# EFuse_5V.net
KiCad netlist of a schematic drawn in Altium Designer
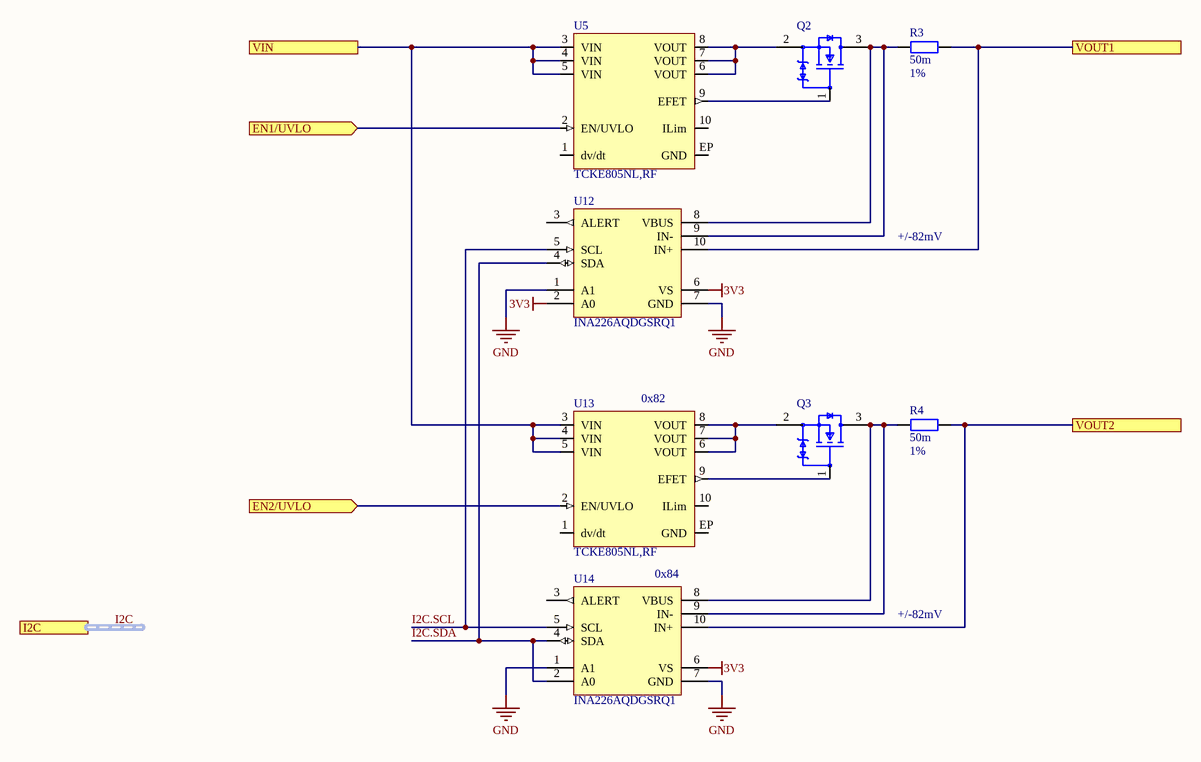
[diagram p0: EFuse_5V.SchDoc]

(export (version "E")
  (design (tool "Eeschema 10.0.6"))
  (components
    (comp (ref "Q2")
      (value "DMG2302UK-7")
      (footprint "SOT23-3-DIODES")
      (description "Transistor: N-MOSFET; unipolar; 20V; 2.2A; 0, 09ohm; 0.66W; -55+150 st.C; SMD; SOT23")
      (libsource (lib "AFR365") (part "87c0c04a04979492222792dd46c39c9"))
    )
    (comp (ref "Q3")
      (value "DMG2302UK-7")
      (footprint "SOT23-3-DIODES")
      (description "Transistor: N-MOSFET; unipolar; 20V; 2.2A; 0, 09ohm; 0.66W; -55+150 st.C; SMD; SOT23")
      (libsource (lib "AFR365") (part "87c0c04a04979492222792dd46c39c9"))
    )
    (comp (ref "R3")
      (value "50m")
      (footprint "SMD_1206_RES")
      (description "RES SMD 0.05 OHM 1% 1 1206 ±100ppm/°C")
      (fields
        (field (name "TOLERANCE") "1%")
        (field (name "POWER") "1W")
        (field (name "Comment") "ERJ-8BWFR050V")
      )
      (libsource (lib "AFR365") (part "resistor"))
    )
    (comp (ref "R4")
      (value "50m")
      (footprint "SMD_1206_RES")
      (description "RES SMD 0.05 OHM 1% 1 1206 ±100ppm/°C")
      (fields
        (field (name "TOLERANCE") "1%")
        (field (name "POWER") "1W")
        (field (name "Comment") "ERJ-8BWFR050V")
      )
      (libsource (lib "AFR365") (part "resistor"))
    )
    (comp (ref "U5")
      (value "TCKE805NL,RF")
      (footprint "WSON10B-Toshiba")
      (description "Hot-Swap Ctrl, Wson-10, -40 To 85Deg C Rohs Compliant: Yes")
      (libsource (lib "AFR365") (part "TCKE812NL,RF"))
    )
    (comp (ref "U12")
      (value "INA226AQDGSRQ1")
      (footprint "TI-DGS0010A-VSSOP-10")
      (description "SP Amp Current Shunt and Power Monitor Dual 5.5V 10-Pin VSSOP T/R")
      (libsource (lib "AFR365") (part "INA228"))
    )
    (comp (ref "U13")
      (value "TCKE805NL,RF")
      (footprint "WSON10B-Toshiba")
      (description "Hot-Swap Ctrl, Wson-10, -40 To 85Deg C Rohs Compliant: Yes")
      (libsource (lib "AFR365") (part "TCKE812NL,RF"))
    )
    (comp (ref "U14")
      (value "INA226AQDGSRQ1")
      (footprint "TI-DGS0010A-VSSOP-10")
      (description "SP Amp Current Shunt and Power Monitor Dual 5.5V 10-Pin VSSOP T/R")
      (libsource (lib "AFR365") (part "INA228"))
    )
  )
  (nets
    (net (code "2") (name "/EN1{slash}UVLO") (class "Default")
      (node (ref "U5") (pin "2") (pinfunction "EN/UVLO_2") (pintype "input"))
    )
    (net (code "3") (name "/EN2{slash}UVLO") (class "Default")
      (node (ref "U13") (pin "2") (pinfunction "EN/UVLO_2") (pintype "input"))
    )
    (net (code "4") (name "/I2C.SCL") (class "Default")
      (node (ref "U12") (pin "5") (pinfunction "SCL_5") (pintype "input"))
      (node (ref "U14") (pin "5") (pinfunction "SCL_5") (pintype "input"))
    )
    (net (code "5") (name "/I2C.SDA") (class "Default")
      (node (ref "U12") (pin "4") (pinfunction "SDA_4") (pintype "bidirectional"))
      (node (ref "U14") (pin "2") (pinfunction "A0_2") (pintype "passive"))
      (node (ref "U14") (pin "4") (pinfunction "SDA_4") (pintype "bidirectional"))
    )
    (net (code "6") (name "/VIN") (class "Default")
      (node (ref "U13") (pin "3") (pinfunction "VIN_3") (pintype "power_in"))
      (node (ref "U13") (pin "4") (pinfunction "VIN_4") (pintype "power_in"))
      (node (ref "U13") (pin "5") (pinfunction "VIN_5") (pintype "power_in"))
      (node (ref "U5") (pin "3") (pinfunction "VIN_3") (pintype "power_in"))
      (node (ref "U5") (pin "4") (pinfunction "VIN_4") (pintype "power_in"))
      (node (ref "U5") (pin "5") (pinfunction "VIN_5") (pintype "power_in"))
    )
    (net (code "7") (name "/VOUT1") (class "Default")
      (node (ref "R3") (pin "2") (pinfunction "2_2") (pintype "passive"))
      (node (ref "U12") (pin "10") (pinfunction "IN+_10") (pintype "power_in"))
    )
    (net (code "8") (name "/VOUT2") (class "Default")
      (node (ref "R4") (pin "2") (pinfunction "2_2") (pintype "passive"))
      (node (ref "U14") (pin "10") (pinfunction "IN+_10") (pintype "power_in"))
    )
    (net (code "10") (name "3V3") (class "Default")
      (node (ref "U12") (pin "2") (pinfunction "A0_2") (pintype "passive"))
      (node (ref "U12") (pin "6") (pinfunction "VS_6") (pintype "power_in"))
      (node (ref "U14") (pin "6") (pinfunction "VS_6") (pintype "power_in"))
    )
    (net (code "11") (name "GND") (class "Default")
      (node (ref "U12") (pin "1") (pinfunction "A1_1") (pintype "passive"))
      (node (ref "U12") (pin "7") (pinfunction "GND_7") (pintype "power_in"))
      (node (ref "U14") (pin "1") (pinfunction "A1_1") (pintype "passive"))
      (node (ref "U14") (pin "7") (pinfunction "GND_7") (pintype "power_in"))
    )
    (net (code "12") (name "Net-(Q2-D)") (class "Default")
      (node (ref "Q2") (pin "3") (pinfunction "D_3") (pintype "passive"))
      (node (ref "R3") (pin "1") (pinfunction "1_1") (pintype "passive"))
      (node (ref "U12") (pin "8") (pinfunction "VBUS_8") (pintype "power_in"))
      (node (ref "U12") (pin "9") (pinfunction "IN-_9") (pintype "power_in"))
    )
    (net (code "13") (name "Net-(Q2-G)") (class "Default")
      (node (ref "Q2") (pin "1") (pinfunction "G_1") (pintype "passive"))
      (node (ref "U5") (pin "9") (pinfunction "EFET_9") (pintype "output"))
    )
    (net (code "14") (name "Net-(Q2-S)") (class "Default")
      (node (ref "Q2") (pin "2") (pinfunction "S_2") (pintype "passive"))
      (node (ref "U5") (pin "6") (pinfunction "VOUT_6") (pintype "power_in"))
      (node (ref "U5") (pin "7") (pinfunction "VOUT_7") (pintype "power_in"))
      (node (ref "U5") (pin "8") (pinfunction "VOUT_8") (pintype "power_in"))
    )
    (net (code "15") (name "Net-(Q3-D)") (class "Default")
      (node (ref "Q3") (pin "3") (pinfunction "D_3") (pintype "passive"))
      (node (ref "R4") (pin "1") (pinfunction "1_1") (pintype "passive"))
      (node (ref "U14") (pin "8") (pinfunction "VBUS_8") (pintype "power_in"))
      (node (ref "U14") (pin "9") (pinfunction "IN-_9") (pintype "power_in"))
    )
    (net (code "16") (name "Net-(Q3-G)") (class "Default")
      (node (ref "Q3") (pin "1") (pinfunction "G_1") (pintype "passive"))
      (node (ref "U13") (pin "9") (pinfunction "EFET_9") (pintype "output"))
    )
    (net (code "17") (name "Net-(Q3-S)") (class "Default")
      (node (ref "Q3") (pin "2") (pinfunction "S_2") (pintype "passive"))
      (node (ref "U13") (pin "6") (pinfunction "VOUT_6") (pintype "power_in"))
      (node (ref "U13") (pin "7") (pinfunction "VOUT_7") (pintype "power_in"))
      (node (ref "U13") (pin "8") (pinfunction "VOUT_8") (pintype "power_in"))
    )
    (net (code "18") (name "unconnected-(U5-GND-PadEP)") (class "Default")
      (node (ref "U5") (pin "EP") (pinfunction "GND_EP") (pintype "passive"))
    )
    (net (code "19") (name "unconnected-(U5-ILim-Pad10)") (class "Default")
      (node (ref "U5") (pin "10") (pinfunction "ILim_10") (pintype "passive"))
    )
    (net (code "20") (name "unconnected-(U5-dv{slash}dt-Pad1)") (class "Default")
      (node (ref "U5") (pin "1") (pinfunction "dv/dt_1") (pintype "passive"))
    )
    (net (code "21") (name "unconnected-(U12-ALERT-Pad3)") (class "Default")
      (node (ref "U12") (pin "3") (pinfunction "ALERT_3") (pintype "output"))
    )
    (net (code "22") (name "unconnected-(U13-GND-PadEP)") (class "Default")
      (node (ref "U13") (pin "EP") (pinfunction "GND_EP") (pintype "passive"))
    )
    (net (code "23") (name "unconnected-(U13-ILim-Pad10)") (class "Default")
      (node (ref "U13") (pin "10") (pinfunction "ILim_10") (pintype "passive"))
    )
    (net (code "24") (name "unconnected-(U13-dv{slash}dt-Pad1)") (class "Default")
      (node (ref "U13") (pin "1") (pinfunction "dv/dt_1") (pintype "passive"))
    )
    (net (code "25") (name "unconnected-(U14-ALERT-Pad3)") (class "Default")
      (node (ref "U14") (pin "3") (pinfunction "ALERT_3") (pintype "output"))
    )
  )
)
